# PM-BAT_v0_5-35X22_86.net
KiCad netlist of a schematic drawn in EAGLE
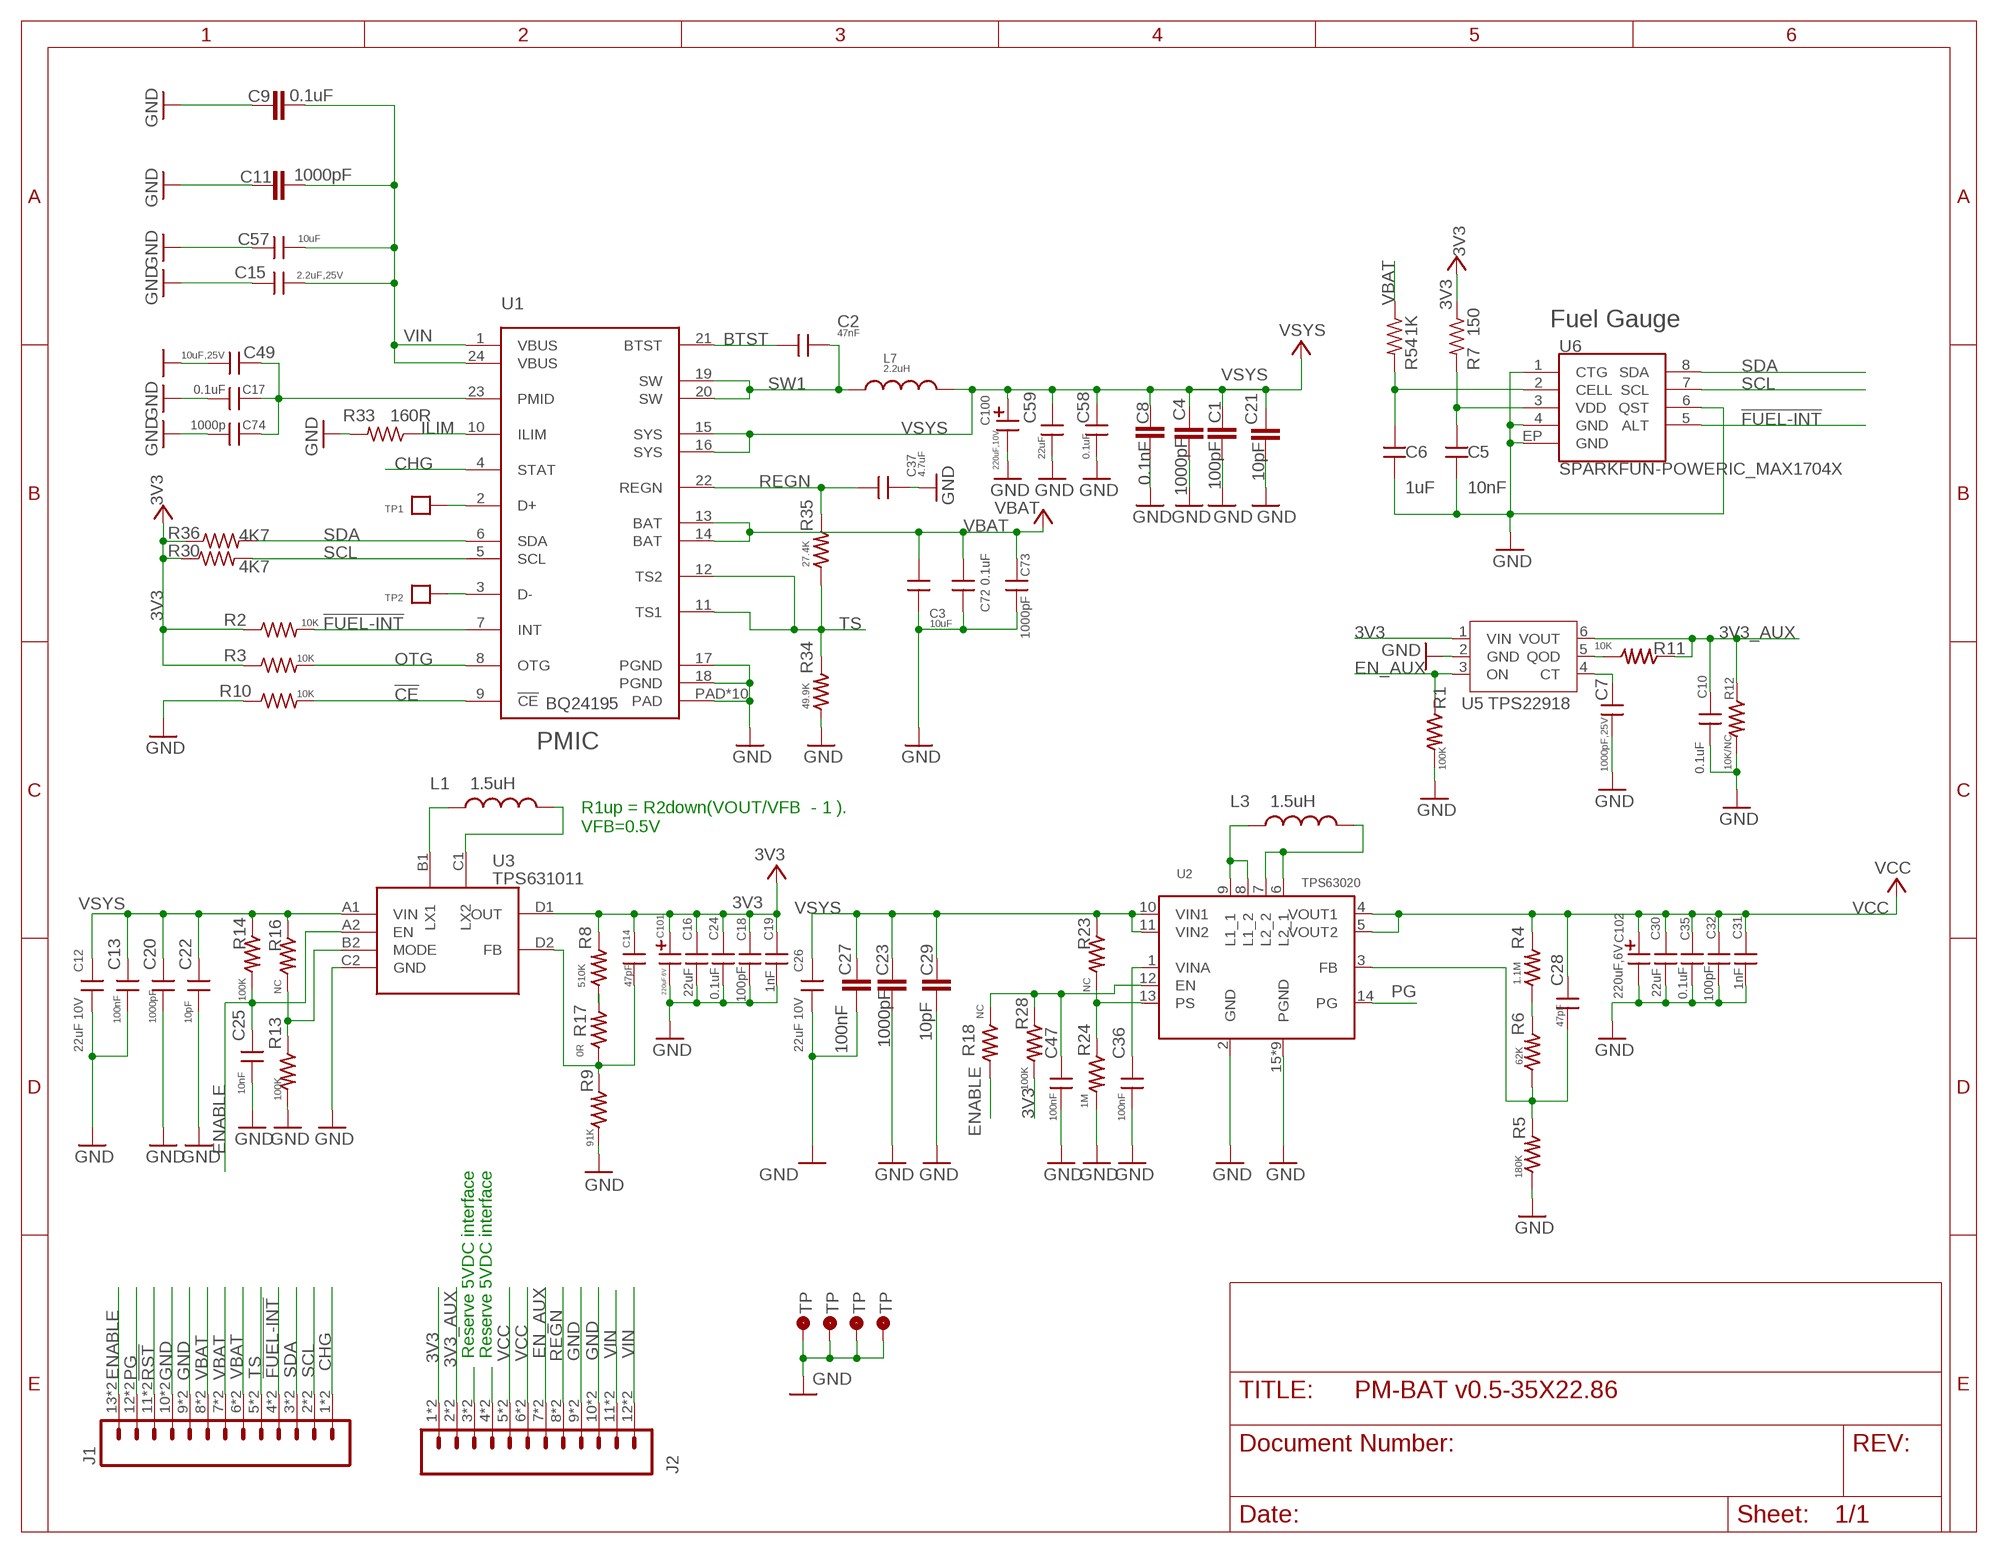
[diagram p0: schematic, sheet 1]

(export (version "E")
  (design (tool "Eeschema 10.0.6"))
  (components
    (comp (ref "C1")
      (value "100pF")
      (footprint "eagle-import:C0402_B")
      (libsource (lib "eagle-import") (part "CAP_1"))
    )
    (comp (ref "C2")
      (value "47nF")
      (footprint "eagle-import:C-0402")
      (libsource (lib "eagle-import") (part "particle SZ_CAP0402"))
    )
    (comp (ref "C3")
      (value "10uF")
      (footprint "eagle-import:C0805")
      (libsource (lib "eagle-import") (part "particle SZ_CAPC0805"))
    )
    (comp (ref "C4")
      (value "1000pF")
      (footprint "eagle-import:C0402_B")
      (libsource (lib "eagle-import") (part "CAP_1"))
    )
    (comp (ref "C5")
      (value "10nF")
      (footprint "eagle-import:C0402")
      (libsource (lib "eagle-import") (part "particle SZ_CAP0402A"))
    )
    (comp (ref "C6")
      (value "1uF")
      (footprint "eagle-import:C0402")
      (libsource (lib "eagle-import") (part "particle SZ_CAP0402A"))
    )
    (comp (ref "C7")
      (value "1000pF,25V")
      (footprint "eagle-import:C0402")
      (libsource (lib "eagle-import") (part "particle SZ_CAP0402A"))
    )
    (comp (ref "C8")
      (value "0.1nF")
      (footprint "eagle-import:C0402_B")
      (libsource (lib "eagle-import") (part "CAP_1"))
    )
    (comp (ref "C9")
      (value "0.1uF")
      (footprint "eagle-import:C0402_B")
      (libsource (lib "eagle-import") (part "CAP_1"))
    )
    (comp (ref "C10")
      (value "0.1uF")
      (footprint "eagle-import:C0201-N")
      (libsource (lib "eagle-import") (part "CAPC0201-N"))
    )
    (comp (ref "C11")
      (value "1000pF")
      (footprint "eagle-import:C0402_B")
      (libsource (lib "eagle-import") (part "CAP_1"))
    )
    (comp (ref "C12")
      (value "22uF 10V")
      (footprint "eagle-import:C0603")
      (libsource (lib "eagle-import") (part "particle SZ_21650216_CAPC0603"))
    )
    (comp (ref "C13")
      (value "100nF")
      (footprint "eagle-import:C0201-N")
      (libsource (lib "eagle-import") (part "CAPC0201-N"))
    )
    (comp (ref "C14")
      (value "47pF")
      (footprint "eagle-import:C0201-N")
      (libsource (lib "eagle-import") (part "CAPC0201-N"))
    )
    (comp (ref "C15")
      (value "2.2uF,25V")
      (footprint "eagle-import:C-0603A")
      (libsource (lib "eagle-import") (part "particle SZ_CAP0603A"))
    )
    (comp (ref "C16")
      (value "22uF")
      (footprint "eagle-import:C-0603A")
      (libsource (lib "eagle-import") (part "particle SZ_21650216_CAP0603A"))
    )
    (comp (ref "C17")
      (value "0.1uF")
      (footprint "eagle-import:C0402")
      (libsource (lib "eagle-import") (part "CAP0402A"))
    )
    (comp (ref "C18")
      (value "100pF")
      (footprint "eagle-import:C0402")
      (libsource (lib "eagle-import") (part "particle SZ_CAP0402A"))
    )
    (comp (ref "C19")
      (value "1nF")
      (footprint "eagle-import:C0402")
      (libsource (lib "eagle-import") (part "particle SZ_CAP0402A"))
    )
    (comp (ref "C20")
      (value "1000pF")
      (footprint "eagle-import:C0201-N")
      (libsource (lib "eagle-import") (part "CAPC0201-N"))
    )
    (comp (ref "C21")
      (value "10pF")
      (footprint "eagle-import:C0402_B")
      (libsource (lib "eagle-import") (part "CAP_1"))
    )
    (comp (ref "C22")
      (value "10pF")
      (footprint "eagle-import:C0201-N")
      (libsource (lib "eagle-import") (part "CAPC0201-N"))
    )
    (comp (ref "C23")
      (value "1000pF")
      (footprint "eagle-import:C0402_B")
      (libsource (lib "eagle-import") (part "CAP_1"))
    )
    (comp (ref "C24")
      (value "0.1uF")
      (footprint "eagle-import:C0402")
      (libsource (lib "eagle-import") (part "particle SZ_CAP0402A"))
    )
    (comp (ref "C25")
      (value "10nF")
      (footprint "eagle-import:C0201-N")
      (libsource (lib "eagle-import") (part "CAPC0201-N"))
    )
    (comp (ref "C26")
      (value "22uF 10V")
      (footprint "eagle-import:C0603")
      (libsource (lib "eagle-import") (part "particle SZ_21650216_CAPC0603"))
    )
    (comp (ref "C27")
      (value "100nF")
      (footprint "eagle-import:C0402_B")
      (libsource (lib "eagle-import") (part "CAP_1"))
    )
    (comp (ref "C28")
      (value "47pF")
      (footprint "eagle-import:C0201-N")
      (libsource (lib "eagle-import") (part "CAPC0201-N"))
    )
    (comp (ref "C29")
      (value "10pF")
      (footprint "eagle-import:C0402_B")
      (libsource (lib "eagle-import") (part "CAP_1"))
    )
    (comp (ref "C30")
      (value "22uF")
      (footprint "eagle-import:C-0603A")
      (libsource (lib "eagle-import") (part "particle SZ_21650216_CAP0603A"))
    )
    (comp (ref "C31")
      (value "1nF")
      (footprint "eagle-import:C0402")
      (libsource (lib "eagle-import") (part "particle SZ_CAP0402A"))
    )
    (comp (ref "C32")
      (value "100pF")
      (footprint "eagle-import:C0402")
      (libsource (lib "eagle-import") (part "particle SZ_CAP0402A"))
    )
    (comp (ref "C35")
      (value "0.1uF")
      (footprint "eagle-import:C0402")
      (libsource (lib "eagle-import") (part "particle SZ_CAP0402A"))
    )
    (comp (ref "C36")
      (value "100nF")
      (footprint "eagle-import:C0201-N")
      (libsource (lib "eagle-import") (part "CAPC0201-N"))
    )
    (comp (ref "C37")
      (value "4.7uF")
      (footprint "eagle-import:C0402")
      (libsource (lib "eagle-import") (part "particle SZ_CAP0402A"))
    )
    (comp (ref "C47")
      (value "100nF")
      (footprint "eagle-import:C0201-N")
      (libsource (lib "eagle-import") (part "CAPC0201-N"))
    )
    (comp (ref "C49")
      (value "10uF,25V")
      (footprint "eagle-import:C-0603A")
      (libsource (lib "eagle-import") (part "particle SZ_CAP0603A"))
    )
    (comp (ref "C57")
      (value "10uF")
      (footprint "eagle-import:C-0603A")
      (libsource (lib "eagle-import") (part "particle SZ_CAP0603A"))
    )
    (comp (ref "C58")
      (value "0.1uF")
      (footprint "eagle-import:C0402")
      (libsource (lib "eagle-import") (part "particle SZ_CAP0402A"))
    )
    (comp (ref "C59")
      (value "22uF")
      (footprint "eagle-import:C0603")
      (libsource (lib "eagle-import") (part "particle SZ_CAPC0603"))
    )
    (comp (ref "C72")
      (value "0.1uF")
      (footprint "eagle-import:C-0402")
      (libsource (lib "eagle-import") (part "particle SZ_CAP0402"))
    )
    (comp (ref "C73")
      (value "1000pF")
      (footprint "eagle-import:C-0402")
      (libsource (lib "eagle-import") (part "particle SZ_CAP0402"))
    )
    (comp (ref "C74")
      (value "1000p")
      (footprint "eagle-import:C-0402")
      (libsource (lib "eagle-import") (part "particle SZ_CAP0402"))
    )
    (comp (ref "C100")
      (value "220uF,10V")
      (footprint "eagle-import:CASE-B")
      (libsource (lib "eagle-import") (part "CAP-ECASE_B"))
    )
    (comp (ref "C101")
      (value "220uF.6V")
      (footprint "eagle-import:CASE-B")
      (libsource (lib "eagle-import") (part "CAP-ECASE_B"))
    )
    (comp (ref "C102")
      (value "220uF,6V")
      (footprint "eagle-import:CASE-B")
      (libsource (lib "eagle-import") (part "CAP-ECASE_B"))
    )
    (comp (ref "J1")
      (value "M13PTH-CST-R")
      (footprint "eagle-import:1X13-CASTELLATED")
      (libsource (lib "eagle-import") (part "M13PTH-CST-R"))
    )
    (comp (ref "J2")
      (value "M12PTH-CST-R")
      (footprint "eagle-import:1X12-CASTELLATED")
      (libsource (lib "eagle-import") (part "M12PTH-CST-R"))
    )
    (comp (ref "L1")
      (value "1.5uH")
      (footprint "eagle-import:INDUCTOR-2520")
      (libsource (lib "eagle-import") (part "INDUCTOR-SPARKFUNINDUCTOR-2520"))
    )
    (comp (ref "L3")
      (value "1.5uH")
      (footprint "eagle-import:INDUCTOR-2520")
      (libsource (lib "eagle-import") (part "INDUCTOR-SPARKFUNINDUCTOR-2520"))
    )
    (comp (ref "L7")
      (value "2.2uH")
      (footprint "eagle-import:INDUCTOR-4040")
      (libsource (lib "eagle-import") (part "INDUCTORI"))
    )
    (comp (ref "R1")
      (value "100K")
      (footprint "eagle-import:R0201-N")
      (libsource (lib "eagle-import") (part "RESR0201-N"))
    )
    (comp (ref "R2")
      (value "10K")
      (footprint "eagle-import:R0402_B")
      (libsource (lib "eagle-import") (part "Spark_R-US_"))
    )
    (comp (ref "R3")
      (value "10K")
      (footprint "eagle-import:R0402_B")
      (libsource (lib "eagle-import") (part "Spark_R-US_"))
    )
    (comp (ref "R4")
      (value "1.1M")
      (footprint "eagle-import:R0201-N")
      (libsource (lib "eagle-import") (part "RESR0201-N"))
    )
    (comp (ref "R5")
      (value "180K")
      (footprint "eagle-import:R0201-N")
      (libsource (lib "eagle-import") (part "RESR0201-N"))
    )
    (comp (ref "R6")
      (value "62K")
      (footprint "eagle-import:R0201-N")
      (libsource (lib "eagle-import") (part "RESR0201-N"))
    )
    (comp (ref "R7")
      (value "150")
      (footprint "eagle-import:R0402_B")
      (libsource (lib "eagle-import") (part "R-US_"))
    )
    (comp (ref "R8")
      (value "510K")
      (footprint "eagle-import:R0201-N")
      (libsource (lib "eagle-import") (part "RESR0201-N"))
    )
    (comp (ref "R9")
      (value "91K")
      (footprint "eagle-import:R0201-N")
      (libsource (lib "eagle-import") (part "RESR0201-N"))
    )
    (comp (ref "R10")
      (value "10K")
      (footprint "eagle-import:R0402_B")
      (libsource (lib "eagle-import") (part "Spark_R-US_"))
    )
    (comp (ref "R11")
      (value "10K")
      (footprint "eagle-import:R0201-N")
      (libsource (lib "eagle-import") (part "RESR0201-N"))
    )
    (comp (ref "R12")
      (value "10K/NC")
      (footprint "eagle-import:R0201-N")
      (libsource (lib "eagle-import") (part "RESR0201-N"))
    )
    (comp (ref "R13")
      (value "100K")
      (footprint "eagle-import:R0201-N")
      (libsource (lib "eagle-import") (part "RESR0201-N"))
    )
    (comp (ref "R14")
      (value "100K")
      (footprint "eagle-import:R0201-N")
      (libsource (lib "eagle-import") (part "RESR0201-N"))
    )
    (comp (ref "R16")
      (value "NC")
      (footprint "eagle-import:R0201-N")
      (libsource (lib "eagle-import") (part "RESR0201-N"))
    )
    (comp (ref "R17")
      (value "0R")
      (footprint "eagle-import:R0201-N")
      (libsource (lib "eagle-import") (part "RESR0201-N"))
    )
    (comp (ref "R18")
      (value "NC")
      (footprint "eagle-import:R0201-N")
      (libsource (lib "eagle-import") (part "RESR0201-N"))
    )
    (comp (ref "R23")
      (value "NC")
      (footprint "eagle-import:R0201-N")
      (libsource (lib "eagle-import") (part "RESR0201-N"))
    )
    (comp (ref "R24")
      (value "1M")
      (footprint "eagle-import:R0201-N")
      (libsource (lib "eagle-import") (part "RESR0201-N"))
    )
    (comp (ref "R28")
      (value "100K")
      (footprint "eagle-import:R0201-N")
      (libsource (lib "eagle-import") (part "RESR0201-N"))
    )
    (comp (ref "R30")
      (value "4K7")
      (footprint "eagle-import:R0402_B")
      (libsource (lib "eagle-import") (part "R-US_"))
    )
    (comp (ref "R33")
      (value "160R")
      (footprint "eagle-import:R0402_B")
      (libsource (lib "eagle-import") (part "R-US_"))
    )
    (comp (ref "R34")
      (value "49.9K")
      (footprint "eagle-import:R0201-N")
      (libsource (lib "eagle-import") (part "RESR0201-N"))
    )
    (comp (ref "R35")
      (value "27.4K")
      (footprint "eagle-import:R0201-N")
      (libsource (lib "eagle-import") (part "RESR0201-N"))
    )
    (comp (ref "R36")
      (value "4K7")
      (footprint "eagle-import:R0402_B")
      (libsource (lib "eagle-import") (part "R-US_"))
    )
    (comp (ref "R54")
      (value "1K")
      (footprint "eagle-import:R0402_B")
      (libsource (lib "eagle-import") (part "R-US_"))
    )
    (comp (ref "TP1")
      (value "TP1311MM")
      (footprint "eagle-import:TP-1311MM")
      (libsource (lib "eagle-import") (part "TP1311MM"))
    )
    (comp (ref "TP2")
      (value "TP1311MM")
      (footprint "eagle-import:TP-1311MM")
      (libsource (lib "eagle-import") (part "TP1311MM"))
    )
    (comp (ref "U$1")
      (value "TP")
      (footprint "eagle-import:TP_2.33X1.37")
      (libsource (lib "eagle-import") (part "TP"))
    )
    (comp (ref "U$2")
      (value "TP")
      (footprint "eagle-import:TP_2.33X1.37")
      (libsource (lib "eagle-import") (part "TP"))
    )
    (comp (ref "U$4")
      (value "TP")
      (footprint "eagle-import:TP_2.33X1.37")
      (libsource (lib "eagle-import") (part "TP"))
    )
    (comp (ref "U$5")
      (value "TP")
      (footprint "eagle-import:TP_2.33X1.37")
      (libsource (lib "eagle-import") (part "TP"))
    )
    (comp (ref "U1")
      (value "BQ24195")
      (footprint "eagle-import:ELECTRON_QFN24")
      (libsource (lib "eagle-import") (part "ELECTRON_BQ24298RTWR"))
    )
    (comp (ref "U2")
      (value "TPS63020")
      (footprint "eagle-import:TPS63020")
      (libsource (lib "eagle-import") (part "TPS63020"))
    )
    (comp (ref "U3")
      (value "TPS631011")
      (footprint "eagle-import:DSBGA")
      (libsource (lib "eagle-import") (part "TPS631010"))
    )
    (comp (ref "U5")
      (value "TPS22918")
      (footprint "eagle-import:SOT-23-6")
      (libsource (lib "eagle-import") (part "TPS22918"))
    )
    (comp (ref "U6")
      (value "SPARKFUN-POWERIC_MAX1704X")
      (footprint "eagle-import:SPARKFUN-POWERIC_TDFN-8")
      (libsource (lib "eagle-import") (part "SPARKFUN-POWERIC_MAX1704X"))
    )
  )
  (nets
    (net (code "1") (name "/3V3_AUX") (class "Default")
      (node (ref "C10") (pin "1") (pinfunction "1_1") (pintype "bidirectional"))
      (node (ref "J2") (pin "2") (pinfunction "2_2") (pintype "passive"))
      (node (ref "J2") (pin "@2") (pinfunction "2_@2") (pintype "passive"))
      (node (ref "R11") (pin "1") (pinfunction "1_1") (pintype "bidirectional"))
      (node (ref "R12") (pin "1") (pinfunction "1_1") (pintype "bidirectional"))
      (node (ref "U5") (pin "6") (pinfunction "VOUT_6") (pintype "bidirectional"))
    )
    (net (code "2") (name "/BTST") (class "Default")
      (node (ref "C2") (pin "1") (pinfunction "1_1") (pintype "bidirectional"))
      (node (ref "U1") (pin "21") (pinfunction "BTST_21") (pintype "bidirectional"))
    )
    (net (code "3") (name "/CHG") (class "Default")
      (node (ref "J1") (pin "1") (pinfunction "1_1") (pintype "passive"))
      (node (ref "J1") (pin "@1") (pinfunction "1_@1") (pintype "passive"))
      (node (ref "U1") (pin "4") (pinfunction "STAT_4") (pintype "bidirectional"))
    )
    (net (code "4") (name "/ENABLE") (class "Default")
      (node (ref "C25") (pin "1") (pinfunction "1_1") (pintype "bidirectional"))
      (node (ref "J1") (pin "13") (pinfunction "13_13") (pintype "passive"))
      (node (ref "J1") (pin "@13") (pinfunction "13_@13") (pintype "passive"))
      (node (ref "R14") (pin "2") (pinfunction "2_2") (pintype "bidirectional"))
      (node (ref "R18") (pin "2") (pinfunction "2_2") (pintype "bidirectional"))
      (node (ref "U3") (pin "A2") (pinfunction "EN_A2") (pintype "bidirectional"))
    )
    (net (code "5") (name "/EN_AUX") (class "Default")
      (node (ref "J2") (pin "7") (pinfunction "7_7") (pintype "passive"))
      (node (ref "J2") (pin "@7") (pinfunction "7_@7") (pintype "passive"))
      (node (ref "R1") (pin "1") (pinfunction "1_1") (pintype "bidirectional"))
      (node (ref "U5") (pin "3") (pinfunction "ON_3") (pintype "bidirectional"))
    )
    (net (code "6") (name "/ILIM") (class "Default")
      (node (ref "R33") (pin "1") (pinfunction "1_1") (pintype "passive"))
      (node (ref "U1") (pin "10") (pinfunction "ILIM_10") (pintype "output"))
    )
    (net (code "7") (name "/OTG") (class "Default")
      (node (ref "R3") (pin "2") (pinfunction "2_2") (pintype "passive"))
      (node (ref "U1") (pin "8") (pinfunction "OTG_8") (pintype "bidirectional"))
    )
    (net (code "8") (name "/PG") (class "Default")
      (node (ref "J1") (pin "12") (pinfunction "12_12") (pintype "passive"))
      (node (ref "J1") (pin "@12") (pinfunction "12_@12") (pintype "passive"))
      (node (ref "U2") (pin "14") (pinfunction "PG_14") (pintype "bidirectional"))
    )
    (net (code "9") (name "/REGN") (class "Default")
      (node (ref "C37") (pin "1") (pinfunction "1_1") (pintype "bidirectional"))
      (node (ref "J2") (pin "8") (pinfunction "8_8") (pintype "passive"))
      (node (ref "J2") (pin "@8") (pinfunction "8_@8") (pintype "passive"))
      (node (ref "R35") (pin "2") (pinfunction "2_2") (pintype "bidirectional"))
      (node (ref "U1") (pin "22") (pinfunction "REGN_22") (pintype "bidirectional"))
    )
    (net (code "10") (name "/SCL") (class "Default")
      (node (ref "J1") (pin "2") (pinfunction "2_2") (pintype "passive"))
      (node (ref "J1") (pin "@2") (pinfunction "2_@2") (pintype "passive"))
      (node (ref "R30") (pin "2") (pinfunction "2_2") (pintype "passive"))
      (node (ref "U1") (pin "5") (pinfunction "SCL_5") (pintype "output"))
      (node (ref "U6") (pin "7") (pinfunction "SCL_7") (pintype "bidirectional"))
    )
    (net (code "11") (name "/SDA") (class "Default")
      (node (ref "J1") (pin "3") (pinfunction "3_3") (pintype "passive"))
      (node (ref "J1") (pin "@3") (pinfunction "3_@3") (pintype "passive"))
      (node (ref "R36") (pin "2") (pinfunction "2_2") (pintype "passive"))
      (node (ref "U1") (pin "6") (pinfunction "SDA_6") (pintype "bidirectional"))
      (node (ref "U6") (pin "8") (pinfunction "SDA_8") (pintype "bidirectional"))
    )
    (net (code "12") (name "/SW1") (class "Default")
      (node (ref "C2") (pin "2") (pinfunction "2_2") (pintype "bidirectional"))
      (node (ref "L7") (pin "P$1") (pinfunction "1_P$1") (pintype "passive"))
      (node (ref "U1") (pin "19") (pinfunction "SW_19") (pintype "power_in"))
      (node (ref "U1") (pin "20") (pinfunction "SW_20") (pintype "power_in"))
    )
    (net (code "13") (name "/TS") (class "Default")
      (node (ref "J1") (pin "5") (pinfunction "5_5") (pintype "passive"))
      (node (ref "J1") (pin "@5") (pinfunction "5_@5") (pintype "passive"))
      (node (ref "R34") (pin "2") (pinfunction "2_2") (pintype "bidirectional"))
      (node (ref "R35") (pin "1") (pinfunction "1_1") (pintype "bidirectional"))
      (node (ref "U1") (pin "11") (pinfunction "TS1_11") (pintype "bidirectional"))
      (node (ref "U1") (pin "12") (pinfunction "TS2_12") (pintype "bidirectional"))
    )
    (net (code "14") (name "/VIN") (class "Default")
      (node (ref "C11") (pin "2") (pinfunction "P$2_2") (pintype "passive"))
      (node (ref "C15") (pin "1") (pinfunction "1_1") (pintype "bidirectional"))
      (node (ref "C57") (pin "1") (pinfunction "1_1") (pintype "bidirectional"))
      (node (ref "C9") (pin "2") (pinfunction "P$2_2") (pintype "passive"))
      (node (ref "J2") (pin "11") (pinfunction "11_11") (pintype "passive"))
      (node (ref "J2") (pin "12") (pinfunction "12_12") (pintype "passive"))
      (node (ref "J2") (pin "@11") (pinfunction "11_@11") (pintype "passive"))
      (node (ref "J2") (pin "@12") (pinfunction "12_@12") (pintype "passive"))
      (node (ref "U1") (pin "1") (pinfunction "VBUS_1") (pintype "power_in"))
      (node (ref "U1") (pin "24") (pinfunction "VBUS_24") (pintype "passive"))
    )
    (net (code "15") (name "/~{CE}") (class "Default")
      (node (ref "R10") (pin "2") (pinfunction "2_2") (pintype "passive"))
      (node (ref "U1") (pin "9") (pinfunction "~{CE}_9") (pintype "output"))
    )
    (net (code "16") (name "/~{FUEL-INT}") (class "Default")
      (node (ref "J1") (pin "4") (pinfunction "4_4") (pintype "passive"))
      (node (ref "J1") (pin "@4") (pinfunction "4_@4") (pintype "passive"))
      (node (ref "R2") (pin "2") (pinfunction "2_2") (pintype "passive"))
      (node (ref "U1") (pin "7") (pinfunction "INT_7") (pintype "bidirectional"))
      (node (ref "U6") (pin "5") (pinfunction "ALT_5") (pintype "bidirectional"))
    )
    (net (code "17") (name "/~{RST}") (class "Default")
      (node (ref "J1") (pin "11") (pinfunction "11_11") (pintype "passive"))
      (node (ref "J1") (pin "@11") (pinfunction "11_@11") (pintype "passive"))
    )
    (net (code "18") (name "3V3") (class "Default")
      (node (ref "C101") (pin "P$1") (pinfunction "1_P$1") (pintype "bidirectional"))
      (node (ref "C14") (pin "1") (pinfunction "1_1") (pintype "bidirectional"))
      (node (ref "C16") (pin "1") (pinfunction "1_1") (pintype "bidirectional"))
      (node (ref "C18") (pin "1") (pinfunction "1_1") (pintype "bidirectional"))
      (node (ref "C19") (pin "1") (pinfunction "1_1") (pintype "bidirectional"))
      (node (ref "C24") (pin "1") (pinfunction "1_1") (pintype "bidirectional"))
      (node (ref "J2") (pin "1") (pinfunction "1_1") (pintype "passive"))
      (node (ref "J2") (pin "@1") (pinfunction "1_@1") (pintype "passive"))
      (node (ref "R2") (pin "1") (pinfunction "1_1") (pintype "passive"))
      (node (ref "R28") (pin "2") (pinfunction "2_2") (pintype "bidirectional"))
      (node (ref "R3") (pin "1") (pinfunction "1_1") (pintype "passive"))
      (node (ref "R30") (pin "1") (pinfunction "1_1") (pintype "passive"))
      (node (ref "R36") (pin "1") (pinfunction "1_1") (pintype "passive"))
      (node (ref "R7") (pin "1") (pinfunction "1_1") (pintype "passive"))
      (node (ref "R8") (pin "2") (pinfunction "2_2") (pintype "bidirectional"))
      (node (ref "U3") (pin "D1") (pinfunction "OUT_D1") (pintype "bidirectional"))
      (node (ref "U5") (pin "1") (pinfunction "VIN_1") (pintype "bidirectional"))
    )
    (net (code "19") (name "GND") (class "Default")
      (node (ref "C1") (pin "1") (pinfunction "P$1_1") (pintype "passive"))
      (node (ref "C10") (pin "2") (pinfunction "2_2") (pintype "bidirectional"))
      (node (ref "C100") (pin "P$2") (pinfunction "2_P$2") (pintype "bidirectional"))
      (node (ref "C101") (pin "P$2") (pinfunction "2_P$2") (pintype "bidirectional"))
      (node (ref "C102") (pin "P$2") (pinfunction "2_P$2") (pintype "bidirectional"))
      (node (ref "C11") (pin "1") (pinfunction "P$1_1") (pintype "passive"))
      (node (ref "C12") (pin "2") (pinfunction "2_2") (pintype "bidirectional"))
      (node (ref "C13") (pin "2") (pinfunction "2_2") (pintype "bidirectional"))
      (node (ref "C15") (pin "2") (pinfunction "2_2") (pintype "bidirectional"))
      (node (ref "C16") (pin "2") (pinfunction "2_2") (pintype "bidirectional"))
      (node (ref "C17") (pin "1") (pinfunction "1_1") (pintype "bidirectional"))
      (node (ref "C18") (pin "2") (pinfunction "2_2") (pintype "bidirectional"))
      (node (ref "C19") (pin "2") (pinfunction "2_2") (pintype "bidirectional"))
      (node (ref "C20") (pin "2") (pinfunction "2_2") (pintype "bidirectional"))
      (node (ref "C21") (pin "1") (pinfunction "P$1_1") (pintype "passive"))
      (node (ref "C22") (pin "2") (pinfunction "2_2") (pintype "bidirectional"))
      (node (ref "C23") (pin "1") (pinfunction "P$1_1") (pintype "passive"))
      (node (ref "C24") (pin "2") (pinfunction "2_2") (pintype "bidirectional"))
      (node (ref "C25") (pin "2") (pinfunction "2_2") (pintype "bidirectional"))
      (node (ref "C26") (pin "2") (pinfunction "2_2") (pintype "bidirectional"))
      (node (ref "C27") (pin "1") (pinfunction "P$1_1") (pintype "passive"))
      (node (ref "C29") (pin "1") (pinfunction "P$1_1") (pintype "passive"))
      (node (ref "C3") (pin "2") (pinfunction "2_2") (pintype "bidirectional"))
      (node (ref "C30") (pin "2") (pinfunction "2_2") (pintype "bidirectional"))
      (node (ref "C31") (pin "2") (pinfunction "2_2") (pintype "bidirectional"))
      (node (ref "C32") (pin "2") (pinfunction "2_2") (pintype "bidirectional"))
      (node (ref "C35") (pin "2") (pinfunction "2_2") (pintype "bidirectional"))
      (node (ref "C36") (pin "2") (pinfunction "2_2") (pintype "bidirectional"))
      (node (ref "C37") (pin "2") (pinfunction "2_2") (pintype "bidirectional"))
      (node (ref "C4") (pin "1") (pinfunction "P$1_1") (pintype "passive"))
      (node (ref "C47") (pin "2") (pinfunction "2_2") (pintype "bidirectional"))
      (node (ref "C49") (pin "2") (pinfunction "2_2") (pintype "bidirectional"))
      (node (ref "C5") (pin "2") (pinfunction "2_2") (pintype "bidirectional"))
      (node (ref "C57") (pin "2") (pinfunction "2_2") (pintype "bidirectional"))
      (node (ref "C58") (pin "2") (pinfunction "2_2") (pintype "bidirectional"))
      (node (ref "C59") (pin "2") (pinfunction "2_2") (pintype "bidirectional"))
      (node (ref "C6") (pin "2") (pinfunction "2_2") (pintype "bidirectional"))
      (node (ref "C7") (pin "2") (pinfunction "2_2") (pintype "bidirectional"))
      (node (ref "C72") (pin "2") (pinfunction "2_2") (pintype "bidirectional"))
      (node (ref "C73") (pin "2") (pinfunction "2_2") (pintype "bidirectional"))
      (node (ref "C74") (pin "1") (pinfunction "1_1") (pintype "bidirectional"))
      (node (ref "C8") (pin "1") (pinfunction "P$1_1") (pintype "passive"))
      (node (ref "C9") (pin "1") (pinfunction "P$1_1") (pintype "passive"))
      (node (ref "J1") (pin "10") (pinfunction "10_10") (pintype "passive"))
      (node (ref "J1") (pin "9") (pinfunction "9_9") (pintype "passive"))
      (node (ref "J1") (pin "@10") (pinfunction "10_@10") (pintype "passive"))
      (node (ref "J1") (pin "@9") (pinfunction "9_@9") (pintype "passive"))
      (node (ref "J2") (pin "10") (pinfunction "10_10") (pintype "passive"))
      (node (ref "J2") (pin "9") (pinfunction "9_9") (pintype "passive"))
      (node (ref "J2") (pin "@10") (pinfunction "10_@10") (pintype "passive"))
      (node (ref "J2") (pin "@9") (pinfunction "9_@9") (pintype "passive"))
      (node (ref "R1") (pin "2") (pinfunction "2_2") (pintype "bidirectional"))
      (node (ref "R10") (pin "1") (pinfunction "1_1") (pintype "passive"))
      (node (ref "R12") (pin "2") (pinfunction "2_2") (pintype "bidirectional"))
      (node (ref "R13") (pin "2") (pinfunction "2_2") (pintype "bidirectional"))
      (node (ref "R24") (pin "2") (pinfunction "2_2") (pintype "bidirectional"))
      (node (ref "R33") (pin "2") (pinfunction "2_2") (pintype "passive"))
      (node (ref "R34") (pin "1") (pinfunction "1_1") (pintype "bidirectional"))
      (node (ref "R5") (pin "1") (pinfunction "1_1") (pintype "bidirectional"))
      (node (ref "R9") (pin "1") (pinfunction "1_1") (pintype "bidirectional"))
      (node (ref "U$1") (pin "1") (pinfunction "TP_1") (pintype "bidirectional"))
      (node (ref "U$2") (pin "1") (pinfunction "TP_1") (pintype "bidirectional"))
      (node (ref "U$4") (pin "1") (pinfunction "TP_1") (pintype "bidirectional"))
      (node (ref "U$5") (pin "1") (pinfunction "TP_1") (pintype "bidirectional"))
      (node (ref "U1") (pin "17") (pinfunction "PGND_17") (pintype "passive"))
      (node (ref "U1") (pin "18") (pinfunction "PGND_18") (pintype "passive"))
      (node (ref "U1") (pin "PAD") (pinfunction "PAD_PAD") (pintype "power_in"))
      (node (ref "U1") (pin "PAD@1") (pinfunction "PAD_PAD@1") (pintype "power_in"))
      (node (ref "U1") (pin "PAD@2") (pinfunction "PAD_PAD@2") (pintype "power_in"))
      (node (ref "U1") (pin "PAD@3") (pinfunction "PAD_PAD@3") (pintype "power_in"))
      (node (ref "U1") (pin "PAD@4") (pinfunction "PAD_PAD@4") (pintype "power_in"))
      (node (ref "U1") (pin "PAD@5") (pinfunction "PAD_PAD@5") (pintype "power_in"))
      (node (ref "U1") (pin "PAD@6") (pinfunction "PAD_PAD@6") (pintype "power_in"))
      (node (ref "U1") (pin "PAD@7") (pinfunction "PAD_PAD@7") (pintype "power_in"))
      (node (ref "U1") (pin "PAD@8") (pinfunction "PAD_PAD@8") (pintype "power_in"))
      (node (ref "U1") (pin "PAD@9") (pinfunction "PAD_PAD@9") (pintype "power_in"))
      (node (ref "U2") (pin "15") (pinfunction "PGND_15") (pintype "bidirectional"))
      (node (ref "U2") (pin "16") (pinfunction "PGND_16") (pintype "bidirectional"))
      (node (ref "U2") (pin "17") (pinfunction "PGND_17") (pintype "bidirectional"))
      (node (ref "U2") (pin "18") (pinfunction "PGND_18") (pintype "bidirectional"))
      (node (ref "U2") (pin "19") (pinfunction "PGND_19") (pintype "bidirectional"))
      (node (ref "U2") (pin "2") (pinfunction "GND_2") (pintype "bidirectional"))
      (node (ref "U2") (pin "20") (pinfunction "PGND_20") (pintype "bidirectional"))
      (node (ref "U2") (pin "21") (pinfunction "PGND_21") (pintype "bidirectional"))
      (node (ref "U2") (pin "22") (pinfunction "PGND_22") (pintype "bidirectional"))
      (node (ref "U2") (pin "23") (pinfunction "PGND_23") (pintype "bidirectional"))
      (node (ref "U3") (pin "C2") (pinfunction "GND_C2") (pintype "bidirectional"))
      (node (ref "U5") (pin "2") (pinfunction "GND_2") (pintype "bidirectional"))
      (node (ref "U6") (pin "1") (pinfunction "CTG_1") (pintype "bidirectional"))
      (node (ref "U6") (pin "4") (pinfunction "GND_4") (pintype "bidirectional"))
      (node (ref "U6") (pin "6") (pinfunction "QST_6") (pintype "bidirectional"))
      (node (ref "U6") (pin "EP") (pinfunction "GND_EP") (pintype "bidirectional"))
    )
    (net (code "20") (name "Net-(J2-3-Pad@3)") (class "Default")
      (node (ref "J2") (pin "3") (pinfunction "3_3") (pintype "passive"))
      (node (ref "J2") (pin "@3") (pinfunction "3_@3") (pintype "passive"))
    )
    (net (code "21") (name "Net-(J2-4-Pad@4)") (class "Default")
      (node (ref "J2") (pin "4") (pinfunction "4_4") (pintype "passive"))
      (node (ref "J2") (pin "@4") (pinfunction "4_@4") (pintype "passive"))
    )
    (net (code "22") (name "Net-(R4-Pad1)") (class "Default")
      (node (ref "R4") (pin "1") (pinfunction "1_1") (pintype "bidirectional"))
      (node (ref "R6") (pin "2") (pinfunction "2_2") (pintype "bidirectional"))
    )
    (net (code "23") (name "Net-(R17-Pad2)") (class "Default")
      (node (ref "R17") (pin "2") (pinfunction "2_2") (pintype "bidirectional"))
      (node (ref "R8") (pin "1") (pinfunction "1_1") (pintype "bidirectional"))
    )
    (net (code "24") (name "Net-(TP1-1)") (class "Default")
      (node (ref "TP1") (pin "P$1") (pinfunction "1_P$1") (pintype "bidirectional"))
      (node (ref "U1") (pin "2") (pinfunction "D+_2") (pintype "output"))
    )
    (net (code "25") (name "Net-(TP2-1)") (class "Default")
      (node (ref "TP2") (pin "P$1") (pinfunction "1_P$1") (pintype "bidirectional"))
      (node (ref "U1") (pin "3") (pinfunction "D-_3") (pintype "output"))
    )
    (net (code "26") (name "Net-(U1-PMID)") (class "Default")
      (node (ref "C17") (pin "2") (pinfunction "2_2") (pintype "bidirectional"))
      (node (ref "C49") (pin "1") (pinfunction "1_1") (pintype "bidirectional"))
      (node (ref "C74") (pin "2") (pinfunction "2_2") (pintype "bidirectional"))
      (node (ref "U1") (pin "23") (pinfunction "PMID_23") (pintype "passive"))
    )
    (net (code "27") (name "Net-(U2-EN)") (class "Default")
      (node (ref "C47") (pin "1") (pinfunction "1_1") (pintype "bidirectional"))
      (node (ref "R18") (pin "1") (pinfunction "1_1") (pintype "bidirectional"))
      (node (ref "R28") (pin "1") (pinfunction "1_1") (pintype "bidirectional"))
      (node (ref "U2") (pin "12") (pinfunction "EN_12") (pintype "bidirectional"))
    )
    (net (code "28") (name "Net-(U2-FB)") (class "Default")
      (node (ref "C28") (pin "2") (pinfunction "2_2") (pintype "bidirectional"))
      (node (ref "R5") (pin "2") (pinfunction "2_2") (pintype "bidirectional"))
      (node (ref "R6") (pin "1") (pinfunction "1_1") (pintype "bidirectional"))
      (node (ref "U2") (pin "3") (pinfunction "FB_3") (pintype "bidirectional"))
    )
    (net (code "29") (name "Net-(U2-L1_1)") (class "Default")
      (node (ref "L3") (pin "1") (pinfunction "1_1") (pintype "passive"))
      (node (ref "U2") (pin "8") (pinfunction "L1_2_8") (pintype "bidirectional"))
      (node (ref "U2") (pin "9") (pinfunction "L1_1_9") (pintype "bidirectional"))
    )
    (net (code "30") (name "Net-(U2-L2_1)") (class "Default")
      (node (ref "L3") (pin "2") (pinfunction "2_2") (pintype "passive"))
      (node (ref "U2") (pin "6") (pinfunction "L2_1_6") (pintype "bidirectional"))
      (node (ref "U2") (pin "7") (pinfunction "L2_2_7") (pintype "bidirectional"))
    )
    (net (code "31") (name "Net-(U2-PS)") (class "Default")
      (node (ref "R23") (pin "2") (pinfunction "2_2") (pintype "bidirectional"))
      (node (ref "R24") (pin "1") (pinfunction "1_1") (pintype "bidirectional"))
      (node (ref "U2") (pin "13") (pinfunction "PS_13") (pintype "bidirectional"))
    )
    (net (code "32") (name "Net-(U2-VINA)") (class "Default")
      (node (ref "C36") (pin "1") (pinfunction "1_1") (pintype "bidirectional"))
      (node (ref "U2") (pin "1") (pinfunction "VINA_1") (pintype "bidirectional"))
    )
    (net (code "33") (name "Net-(U3-FB)") (class "Default")
      (node (ref "C14") (pin "2") (pinfunction "2_2") (pintype "bidirectional"))
      (node (ref "R17") (pin "1") (pinfunction "1_1") (pintype "bidirectional"))
      (node (ref "R9") (pin "2") (pinfunction "2_2") (pintype "bidirectional"))
      (node (ref "U3") (pin "D2") (pinfunction "FB_D2") (pintype "bidirectional"))
    )
    (net (code "34") (name "Net-(U3-LX1)") (class "Default")
      (node (ref "L1") (pin "1") (pinfunction "1_1") (pintype "passive"))
      (node (ref "U3") (pin "B1") (pinfunction "LX1_B1") (pintype "bidirectional"))
    )
    (net (code "35") (name "Net-(U3-LX2)") (class "Default")
      (node (ref "L1") (pin "2") (pinfunction "2_2") (pintype "passive"))
      (node (ref "U3") (pin "C1") (pinfunction "LX2_C1") (pintype "bidirectional"))
    )
    (net (code "36") (name "Net-(U3-MODE)") (class "Default")
      (node (ref "R13") (pin "1") (pinfunction "1_1") (pintype "bidirectional"))
      (node (ref "R16") (pin "2") (pinfunction "2_2") (pintype "bidirectional"))
      (node (ref "U3") (pin "B2") (pinfunction "MODE_B2") (pintype "bidirectional"))
    )
    (net (code "37") (name "Net-(U5-CT)") (class "Default")
      (node (ref "C7") (pin "1") (pinfunction "1_1") (pintype "bidirectional"))
      (node (ref "U5") (pin "4") (pinfunction "CT_4") (pintype "bidirectional"))
    )
    (net (code "38") (name "Net-(U5-QOD)") (class "Default")
      (node (ref "R11") (pin "2") (pinfunction "2_2") (pintype "bidirectional"))
      (node (ref "U5") (pin "5") (pinfunction "QOD_5") (pintype "bidirectional"))
    )
    (net (code "39") (name "Net-(U6-CELL)") (class "Default")
      (node (ref "C6") (pin "1") (pinfunction "1_1") (pintype "bidirectional"))
      (node (ref "R54") (pin "2") (pinfunction "2_2") (pintype "passive"))
      (node (ref "U6") (pin "2") (pinfunction "CELL_2") (pintype "bidirectional"))
    )
    (net (code "40") (name "Net-(U6-VDD)") (class "Default")
      (node (ref "C5") (pin "1") (pinfunction "1_1") (pintype "bidirectional"))
      (node (ref "R7") (pin "2") (pinfunction "2_2") (pintype "passive"))
      (node (ref "U6") (pin "3") (pinfunction "VDD_3") (pintype "bidirectional"))
    )
    (net (code "41") (name "VBAT") (class "Default")
      (node (ref "C3") (pin "1") (pinfunction "1_1") (pintype "bidirectional"))
      (node (ref "C72") (pin "1") (pinfunction "1_1") (pintype "bidirectional"))
      (node (ref "C73") (pin "1") (pinfunction "1_1") (pintype "bidirectional"))
      (node (ref "J1") (pin "6") (pinfunction "6_6") (pintype "passive"))
      (node (ref "J1") (pin "7") (pinfunction "7_7") (pintype "passive"))
      (node (ref "J1") (pin "8") (pinfunction "8_8") (pintype "passive"))
      (node (ref "J1") (pin "@6") (pinfunction "6_@6") (pintype "passive"))
      (node (ref "J1") (pin "@7") (pinfunction "7_@7") (pintype "passive"))
      (node (ref "J1") (pin "@8") (pinfunction "8_@8") (pintype "passive"))
      (node (ref "R54") (pin "1") (pinfunction "1_1") (pintype "passive"))
      (node (ref "U1") (pin "13") (pinfunction "BAT_13") (pintype "passive"))
      (node (ref "U1") (pin "14") (pinfunction "BAT_14") (pintype "power_in"))
    )
    (net (code "42") (name "VCC") (class "Default")
      (node (ref "C102") (pin "P$1") (pinfunction "1_P$1") (pintype "bidirectional"))
      (node (ref "C28") (pin "1") (pinfunction "1_1") (pintype "bidirectional"))
      (node (ref "C30") (pin "1") (pinfunction "1_1") (pintype "bidirectional"))
      (node (ref "C31") (pin "1") (pinfunction "1_1") (pintype "bidirectional"))
      (node (ref "C32") (pin "1") (pinfunction "1_1") (pintype "bidirectional"))
      (node (ref "C35") (pin "1") (pinfunction "1_1") (pintype "bidirectional"))
      (node (ref "J2") (pin "5") (pinfunction "5_5") (pintype "passive"))
      (node (ref "J2") (pin "6") (pinfunction "6_6") (pintype "passive"))
      (node (ref "J2") (pin "@5") (pinfunction "5_@5") (pintype "passive"))
      (node (ref "J2") (pin "@6") (pinfunction "6_@6") (pintype "passive"))
      (node (ref "R4") (pin "2") (pinfunction "2_2") (pintype "bidirectional"))
      (node (ref "U2") (pin "4") (pinfunction "VOUT1_4") (pintype "bidirectional"))
      (node (ref "U2") (pin "5") (pinfunction "VOUT2_5") (pintype "bidirectional"))
    )
    (net (code "43") (name "VSYS") (class "Default")
      (node (ref "C1") (pin "2") (pinfunction "P$2_2") (pintype "passive"))
      (node (ref "C100") (pin "P$1") (pinfunction "1_P$1") (pintype "bidirectional"))
      (node (ref "C12") (pin "1") (pinfunction "1_1") (pintype "bidirectional"))
      (node (ref "C13") (pin "1") (pinfunction "1_1") (pintype "bidirectional"))
      (node (ref "C20") (pin "1") (pinfunction "1_1") (pintype "bidirectional"))
      (node (ref "C21") (pin "2") (pinfunction "P$2_2") (pintype "passive"))
      (node (ref "C22") (pin "1") (pinfunction "1_1") (pintype "bidirectional"))
      (node (ref "C23") (pin "2") (pinfunction "P$2_2") (pintype "passive"))
      (node (ref "C26") (pin "1") (pinfunction "1_1") (pintype "bidirectional"))
      (node (ref "C27") (pin "2") (pinfunction "P$2_2") (pintype "passive"))
      (node (ref "C29") (pin "2") (pinfunction "P$2_2") (pintype "passive"))
      (node (ref "C4") (pin "2") (pinfunction "P$2_2") (pintype "passive"))
      (node (ref "C58") (pin "1") (pinfunction "1_1") (pintype "bidirectional"))
      (node (ref "C59") (pin "1") (pinfunction "1_1") (pintype "bidirectional"))
      (node (ref "C8") (pin "2") (pinfunction "P$2_2") (pintype "passive"))
      (node (ref "L7") (pin "P$2") (pinfunction "2_P$2") (pintype "passive"))
      (node (ref "R14") (pin "1") (pinfunction "1_1") (pintype "bidirectional"))
      (node (ref "R16") (pin "1") (pinfunction "1_1") (pintype "bidirectional"))
      (node (ref "R23") (pin "1") (pinfunction "1_1") (pintype "bidirectional"))
      (node (ref "U1") (pin "15") (pinfunction "SYS_15") (pintype "power_in"))
      (node (ref "U1") (pin "16") (pinfunction "SYS_16") (pintype "power_in"))
      (node (ref "U2") (pin "10") (pinfunction "VIN1_10") (pintype "bidirectional"))
      (node (ref "U2") (pin "11") (pinfunction "VIN2_11") (pintype "bidirectional"))
      (node (ref "U3") (pin "A1") (pinfunction "VIN_A1") (pintype "bidirectional"))
    )
  )
)
